# USB_Miner.net
KiCad netlist of a schematic drawn in EAGLE
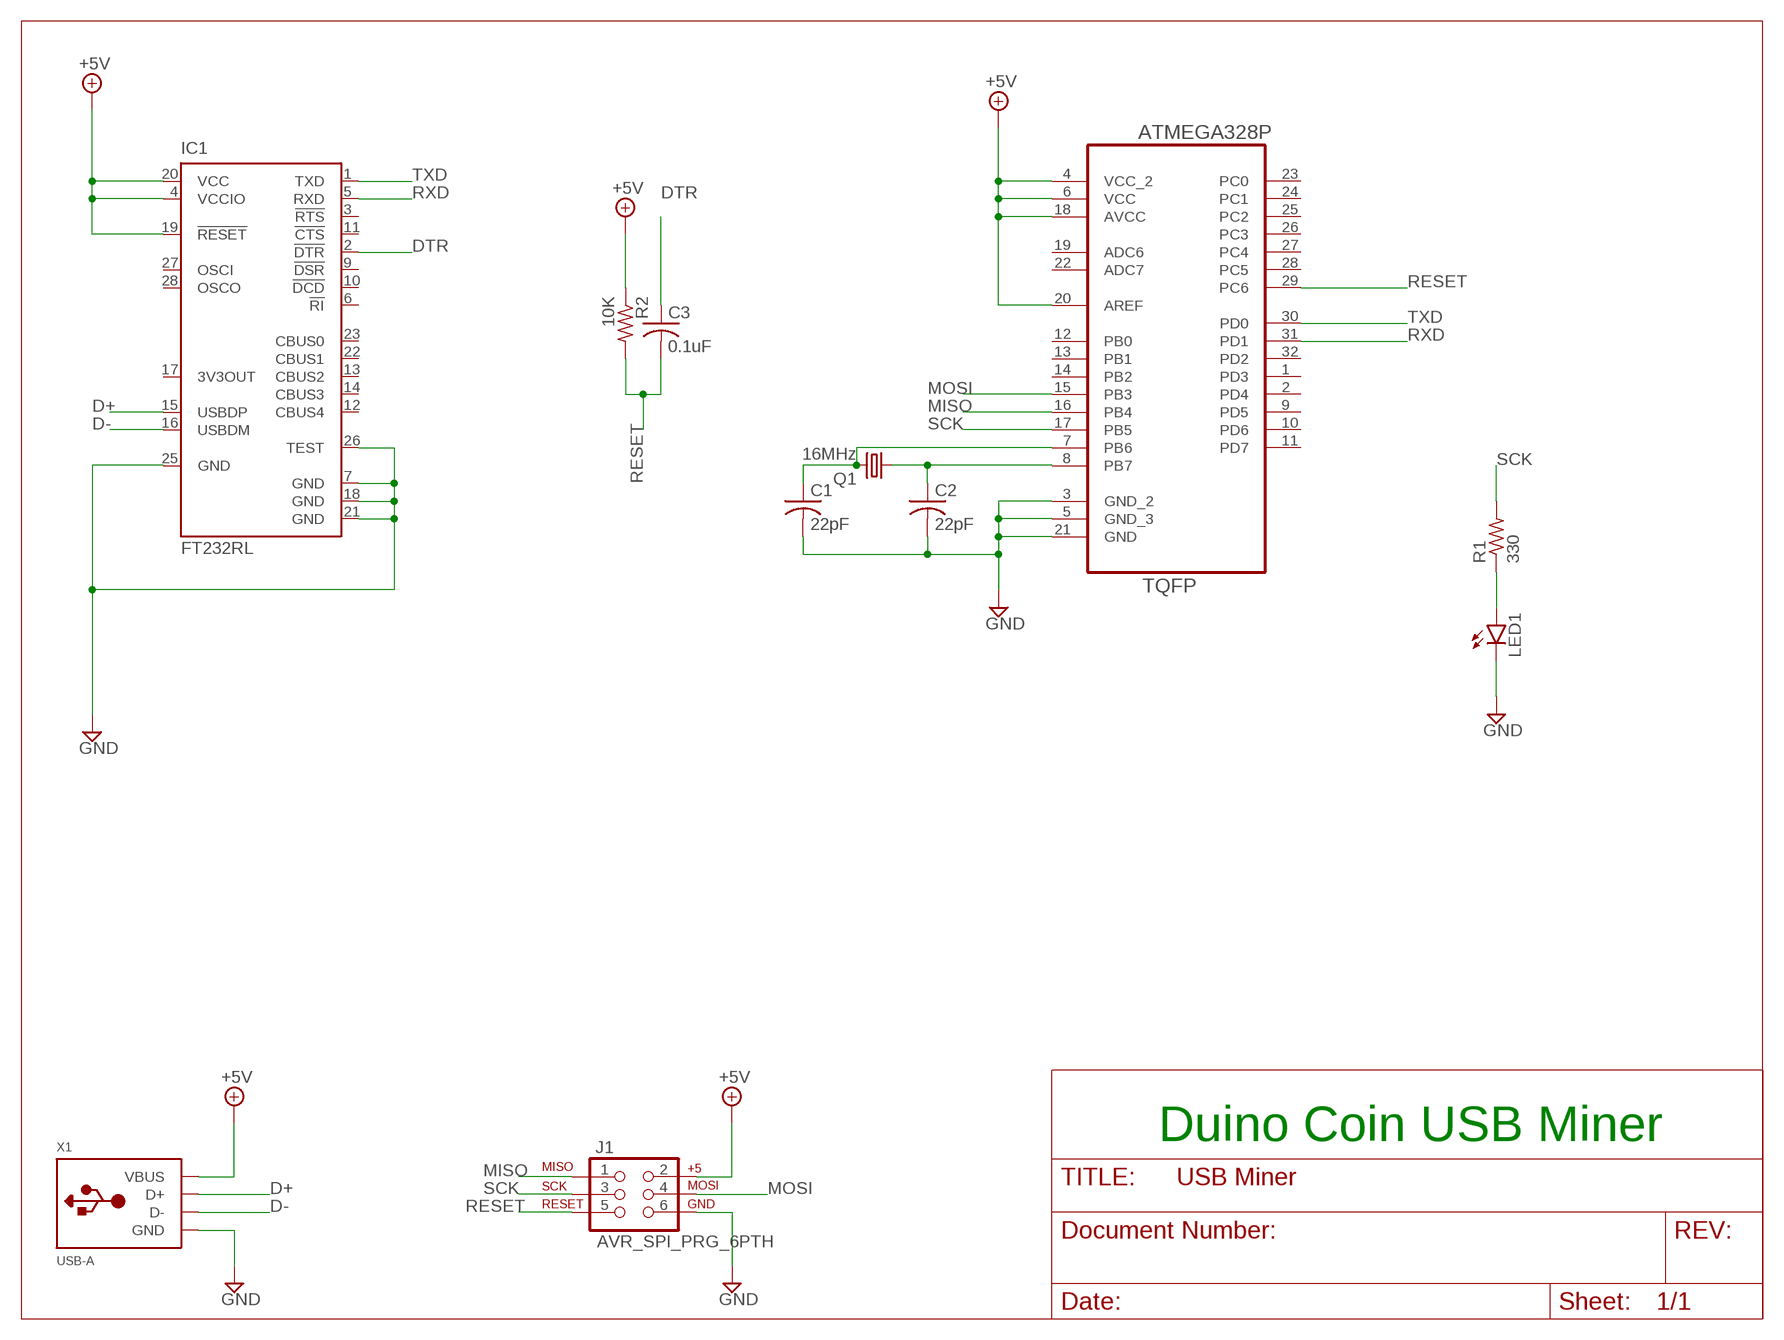
[diagram p0: schematic, sheet 1]

(export (version "E")
  (design (tool "Eeschema 10.0.6"))
  (components
    (comp (ref "C1")
      (value "22pF")
      (footprint "eagle-import:C0805")
      (libsource (lib "eagle-import") (part "C-USC0805"))
    )
    (comp (ref "C2")
      (value "22pF")
      (footprint "eagle-import:C0805")
      (libsource (lib "eagle-import") (part "C-USC0805"))
    )
    (comp (ref "C3")
      (value "0.1uF")
      (footprint "eagle-import:C0805")
      (libsource (lib "eagle-import") (part "C-USC0805"))
    )
    (comp (ref "IC1")
      (value "FT232RL")
      (footprint "eagle-import:SSOP28")
      (libsource (lib "eagle-import") (part "FT232RL"))
    )
    (comp (ref "J1")
      (value "AVR_SPI_PRG_6PTH")
      (footprint "eagle-import:2X3")
      (libsource (lib "eagle-import") (part "AVR_SPI_PRG_6PTH"))
    )
    (comp (ref "LED1")
      (value "LEDCHIP-LED0805")
      (footprint "eagle-import:CHIP-LED0805")
      (libsource (lib "eagle-import") (part "LEDCHIP-LED0805"))
    )
    (comp (ref "Q1")
      (value "16MHz")
      (footprint "eagle-import:CTS406")
      (libsource (lib "eagle-import") (part "CRYSTALCTS406"))
    )
    (comp (ref "R1")
      (value "330")
      (footprint "eagle-import:M0805")
      (libsource (lib "eagle-import") (part "R-US_M0805"))
    )
    (comp (ref "R2")
      (value "10K")
      (footprint "eagle-import:M0805")
      (libsource (lib "eagle-import") (part "R-US_M0805"))
    )
    (comp (ref "U1")
      (value "ATMEGA328P-AU")
      (footprint "eagle-import:QFP80P900X900X120-32N")
      (libsource (lib "eagle-import") (part "ATMEGA328P-AU"))
    )
    (comp (ref "X1")
      (value "USB-A")
      (footprint "eagle-import:MOLEX_480371000")
      (libsource (lib "eagle-import") (part "USB-A"))
    )
  )
  (nets
    (net (code "1") (name "+5V") (class "Default")
      (node (ref "IC1") (pin "19") (pinfunction "~{RESET}_19") (pintype "input"))
      (node (ref "IC1") (pin "20") (pinfunction "VCC_20") (pintype "power_in"))
      (node (ref "IC1") (pin "4") (pinfunction "VCCIO_4") (pintype "power_in"))
      (node (ref "J1") (pin "2") (pinfunction "2_2") (pintype "passive"))
      (node (ref "R2") (pin "1") (pinfunction "1_1") (pintype "passive"))
      (node (ref "U1") (pin "18") (pinfunction "AVCC_18") (pintype "power_in"))
      (node (ref "U1") (pin "20") (pinfunction "AREF_20") (pintype "input"))
      (node (ref "U1") (pin "4") (pinfunction "VCC_2_4") (pintype "power_in"))
      (node (ref "U1") (pin "6") (pinfunction "VCC_6") (pintype "power_in"))
      (node (ref "X1") (pin "1") (pinfunction "VBUS_1") (pintype "power_in"))
    )
    (net (code "2") (name "/D+") (class "Default")
      (node (ref "IC1") (pin "15") (pinfunction "USBDP_15") (pintype "bidirectional"))
      (node (ref "X1") (pin "3") (pinfunction "D+_3") (pintype "bidirectional"))
    )
    (net (code "3") (name "/D-") (class "Default")
      (node (ref "IC1") (pin "16") (pinfunction "USBDM_16") (pintype "bidirectional"))
      (node (ref "X1") (pin "2") (pinfunction "D-_2") (pintype "bidirectional"))
    )
    (net (code "4") (name "/DTR") (class "Default")
      (node (ref "C3") (pin "1") (pinfunction "1_1") (pintype "passive"))
      (node (ref "IC1") (pin "2") (pinfunction "~{DTR}_2") (pintype "output"))
    )
    (net (code "5") (name "/MISO") (class "Default")
      (node (ref "J1") (pin "1") (pinfunction "1_1") (pintype "passive"))
      (node (ref "U1") (pin "16") (pinfunction "PB4_16") (pintype "bidirectional"))
    )
    (net (code "6") (name "/MOSI") (class "Default")
      (node (ref "J1") (pin "4") (pinfunction "4_4") (pintype "passive"))
      (node (ref "U1") (pin "15") (pinfunction "PB3_15") (pintype "bidirectional"))
    )
    (net (code "7") (name "/RESET") (class "Default")
      (node (ref "C3") (pin "2") (pinfunction "2_2") (pintype "passive"))
      (node (ref "J1") (pin "5") (pinfunction "5_5") (pintype "passive"))
      (node (ref "R2") (pin "2") (pinfunction "2_2") (pintype "passive"))
      (node (ref "U1") (pin "29") (pinfunction "PC6_29") (pintype "bidirectional"))
    )
    (net (code "8") (name "/RXD") (class "Default")
      (node (ref "IC1") (pin "5") (pinfunction "RXD_5") (pintype "input"))
      (node (ref "U1") (pin "31") (pinfunction "PD1_31") (pintype "bidirectional"))
    )
    (net (code "9") (name "/SCK") (class "Default")
      (node (ref "J1") (pin "3") (pinfunction "3_3") (pintype "passive"))
      (node (ref "R1") (pin "2") (pinfunction "2_2") (pintype "passive"))
      (node (ref "U1") (pin "17") (pinfunction "PB5_17") (pintype "bidirectional"))
    )
    (net (code "10") (name "/TXD") (class "Default")
      (node (ref "IC1") (pin "1") (pinfunction "TXD_1") (pintype "output"))
      (node (ref "U1") (pin "30") (pinfunction "PD0_30") (pintype "bidirectional"))
    )
    (net (code "11") (name "GND") (class "Default")
      (node (ref "C1") (pin "2") (pinfunction "2_2") (pintype "passive"))
      (node (ref "C2") (pin "2") (pinfunction "2_2") (pintype "passive"))
      (node (ref "IC1") (pin "18") (pinfunction "GND_18") (pintype "power_in"))
      (node (ref "IC1") (pin "21") (pinfunction "GND_21") (pintype "power_in"))
      (node (ref "IC1") (pin "25") (pinfunction "GND_25") (pintype "power_in"))
      (node (ref "IC1") (pin "26") (pinfunction "TEST_26") (pintype "input"))
      (node (ref "IC1") (pin "7") (pinfunction "GND_7") (pintype "power_in"))
      (node (ref "J1") (pin "6") (pinfunction "6_6") (pintype "passive"))
      (node (ref "LED1") (pin "C") (pinfunction "C_C") (pintype "passive"))
      (node (ref "U1") (pin "21") (pinfunction "GND_21") (pintype "passive"))
      (node (ref "U1") (pin "3") (pinfunction "GND_2_3") (pintype "passive"))
      (node (ref "U1") (pin "5") (pinfunction "GND_3_5") (pintype "passive"))
      (node (ref "X1") (pin "4") (pinfunction "GND_4") (pintype "power_in"))
    )
    (net (code "12") (name "Net-(LED1-PadA)") (class "Default")
      (node (ref "LED1") (pin "A") (pinfunction "A_A") (pintype "passive"))
      (node (ref "R1") (pin "1") (pinfunction "1_1") (pintype "passive"))
    )
    (net (code "13") (name "Net-(Q1-2)") (class "Default")
      (node (ref "C1") (pin "1") (pinfunction "1_1") (pintype "passive"))
      (node (ref "Q1") (pin "3") (pinfunction "2_3") (pintype "passive"))
      (node (ref "U1") (pin "7") (pinfunction "PB6_7") (pintype "bidirectional"))
    )
    (net (code "14") (name "Net-(U1-PB7)") (class "Default")
      (node (ref "C2") (pin "1") (pinfunction "1_1") (pintype "passive"))
      (node (ref "Q1") (pin "1") (pinfunction "1_1") (pintype "passive"))
      (node (ref "U1") (pin "8") (pinfunction "PB7_8") (pintype "bidirectional"))
    )
    (net (code "15") (name "unconnected-(IC1-3V3OUT-Pad17)") (class "Default")
      (node (ref "IC1") (pin "17") (pinfunction "3V3OUT_17") (pintype "output"))
    )
    (net (code "16") (name "unconnected-(IC1-CBUS0-Pad23)") (class "Default")
      (node (ref "IC1") (pin "23") (pinfunction "CBUS0_23") (pintype "bidirectional"))
    )
    (net (code "17") (name "unconnected-(IC1-CBUS1-Pad22)") (class "Default")
      (node (ref "IC1") (pin "22") (pinfunction "CBUS1_22") (pintype "bidirectional"))
    )
    (net (code "18") (name "unconnected-(IC1-CBUS2-Pad13)") (class "Default")
      (node (ref "IC1") (pin "13") (pinfunction "CBUS2_13") (pintype "bidirectional"))
    )
    (net (code "19") (name "unconnected-(IC1-CBUS3-Pad14)") (class "Default")
      (node (ref "IC1") (pin "14") (pinfunction "CBUS3_14") (pintype "bidirectional"))
    )
    (net (code "20") (name "unconnected-(IC1-CBUS4-Pad12)") (class "Default")
      (node (ref "IC1") (pin "12") (pinfunction "CBUS4_12") (pintype "bidirectional"))
    )
    (net (code "21") (name "unconnected-(IC1-OSCI-Pad27)") (class "Default")
      (node (ref "IC1") (pin "27") (pinfunction "OSCI_27") (pintype "input"))
    )
    (net (code "22") (name "unconnected-(IC1-OSCO-Pad28)") (class "Default")
      (node (ref "IC1") (pin "28") (pinfunction "OSCO_28") (pintype "output"))
    )
    (net (code "23") (name "unconnected-(IC1-~{CTS}-Pad11)") (class "Default")
      (node (ref "IC1") (pin "11") (pinfunction "~{CTS}_11") (pintype "input"))
    )
    (net (code "24") (name "unconnected-(IC1-~{DCD}-Pad10)") (class "Default")
      (node (ref "IC1") (pin "10") (pinfunction "~{DCD}_10") (pintype "input"))
    )
    (net (code "25") (name "unconnected-(IC1-~{DSR}-Pad9)") (class "Default")
      (node (ref "IC1") (pin "9") (pinfunction "~{DSR}_9") (pintype "input"))
    )
    (net (code "26") (name "unconnected-(IC1-~{RI}-Pad6)") (class "Default")
      (node (ref "IC1") (pin "6") (pinfunction "~{RI}_6") (pintype "input"))
    )
    (net (code "27") (name "unconnected-(IC1-~{RTS}-Pad3)") (class "Default")
      (node (ref "IC1") (pin "3") (pinfunction "~{RTS}_3") (pintype "output"))
    )
    (net (code "28") (name "unconnected-(U1-ADC6-Pad19)") (class "Default")
      (node (ref "U1") (pin "19") (pinfunction "ADC6_19") (pintype "input"))
    )
    (net (code "29") (name "unconnected-(U1-ADC7-Pad22)") (class "Default")
      (node (ref "U1") (pin "22") (pinfunction "ADC7_22") (pintype "input"))
    )
    (net (code "30") (name "unconnected-(U1-PB0-Pad12)") (class "Default")
      (node (ref "U1") (pin "12") (pinfunction "PB0_12") (pintype "bidirectional"))
    )
    (net (code "31") (name "unconnected-(U1-PB1-Pad13)") (class "Default")
      (node (ref "U1") (pin "13") (pinfunction "PB1_13") (pintype "bidirectional"))
    )
    (net (code "32") (name "unconnected-(U1-PB2-Pad14)") (class "Default")
      (node (ref "U1") (pin "14") (pinfunction "PB2_14") (pintype "bidirectional"))
    )
    (net (code "33") (name "unconnected-(U1-PC0-Pad23)") (class "Default")
      (node (ref "U1") (pin "23") (pinfunction "PC0_23") (pintype "bidirectional"))
    )
    (net (code "34") (name "unconnected-(U1-PC1-Pad24)") (class "Default")
      (node (ref "U1") (pin "24") (pinfunction "PC1_24") (pintype "bidirectional"))
    )
    (net (code "35") (name "unconnected-(U1-PC2-Pad25)") (class "Default")
      (node (ref "U1") (pin "25") (pinfunction "PC2_25") (pintype "bidirectional"))
    )
    (net (code "36") (name "unconnected-(U1-PC3-Pad26)") (class "Default")
      (node (ref "U1") (pin "26") (pinfunction "PC3_26") (pintype "bidirectional"))
    )
    (net (code "37") (name "unconnected-(U1-PC4-Pad27)") (class "Default")
      (node (ref "U1") (pin "27") (pinfunction "PC4_27") (pintype "bidirectional"))
    )
    (net (code "38") (name "unconnected-(U1-PC5-Pad28)") (class "Default")
      (node (ref "U1") (pin "28") (pinfunction "PC5_28") (pintype "bidirectional"))
    )
    (net (code "39") (name "unconnected-(U1-PD2-Pad32)") (class "Default")
      (node (ref "U1") (pin "32") (pinfunction "PD2_32") (pintype "bidirectional"))
    )
    (net (code "40") (name "unconnected-(U1-PD3-Pad1)") (class "Default")
      (node (ref "U1") (pin "1") (pinfunction "PD3_1") (pintype "bidirectional"))
    )
    (net (code "41") (name "unconnected-(U1-PD4-Pad2)") (class "Default")
      (node (ref "U1") (pin "2") (pinfunction "PD4_2") (pintype "bidirectional"))
    )
    (net (code "42") (name "unconnected-(U1-PD5-Pad9)") (class "Default")
      (node (ref "U1") (pin "9") (pinfunction "PD5_9") (pintype "bidirectional"))
    )
    (net (code "43") (name "unconnected-(U1-PD6-Pad10)") (class "Default")
      (node (ref "U1") (pin "10") (pinfunction "PD6_10") (pintype "bidirectional"))
    )
    (net (code "44") (name "unconnected-(U1-PD7-Pad11)") (class "Default")
      (node (ref "U1") (pin "11") (pinfunction "PD7_11") (pintype "bidirectional"))
    )
  )
)
